# rgbwa_controller.net
KiCad netlist of a schematic drawn in EAGLE
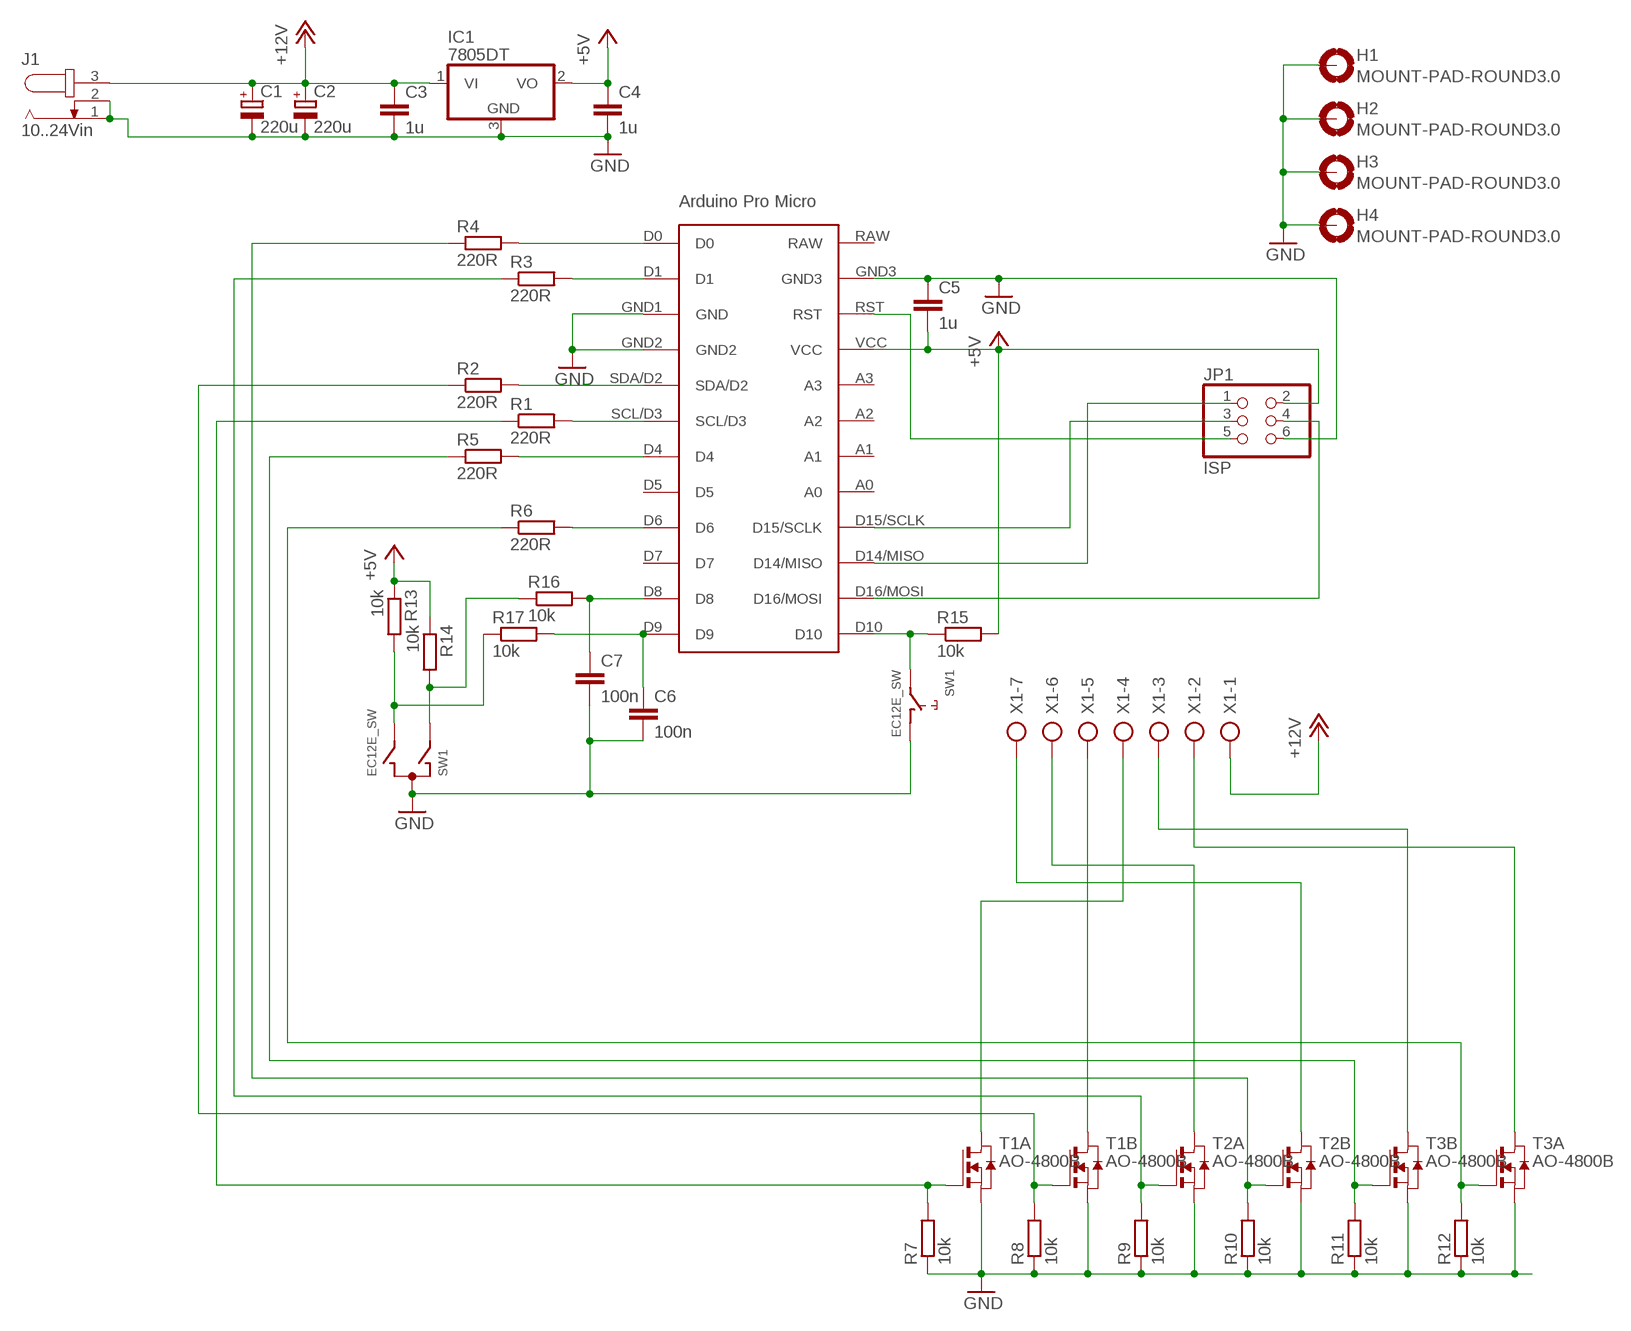
[diagram p0: schematic, sheet 1]

(export (version "E")
  (design (tool "Eeschema 10.0.6"))
  (components
    (comp (ref "C1")
      (value "220u")
      (footprint "eagle-import:150CLZ-1010")
      (libsource (lib "eagle-import") (part "CPOL-EU150CLZ-1010"))
    )
    (comp (ref "C2")
      (value "220u")
      (footprint "eagle-import:150CLZ-1010")
      (libsource (lib "eagle-import") (part "CPOL-EU150CLZ-1010"))
    )
    (comp (ref "C3")
      (value "1u")
      (footprint "eagle-import:C1206")
      (libsource (lib "eagle-import") (part "C-EUC1206"))
    )
    (comp (ref "C4")
      (value "1u")
      (footprint "eagle-import:C1206")
      (libsource (lib "eagle-import") (part "C-EUC1206"))
    )
    (comp (ref "C5")
      (value "1u")
      (footprint "eagle-import:C1206")
      (libsource (lib "eagle-import") (part "C-EUC1206"))
    )
    (comp (ref "C6")
      (value "100n")
      (footprint "eagle-import:C0805")
      (libsource (lib "eagle-import") (part "C-EUC0805"))
    )
    (comp (ref "C7")
      (value "100n")
      (footprint "eagle-import:C0805")
      (libsource (lib "eagle-import") (part "C-EUC0805"))
    )
    (comp (ref "H1")
      (value "MOUNT-PAD-ROUND3.0")
      (footprint "eagle-import:3,0-PAD")
      (libsource (lib "eagle-import") (part "MOUNT-PAD-ROUND3.0"))
    )
    (comp (ref "H2")
      (value "MOUNT-PAD-ROUND3.0")
      (footprint "eagle-import:3,0-PAD")
      (libsource (lib "eagle-import") (part "MOUNT-PAD-ROUND3.0"))
    )
    (comp (ref "H3")
      (value "MOUNT-PAD-ROUND3.0")
      (footprint "eagle-import:3,0-PAD")
      (libsource (lib "eagle-import") (part "MOUNT-PAD-ROUND3.0"))
    )
    (comp (ref "H4")
      (value "MOUNT-PAD-ROUND3.0")
      (footprint "eagle-import:3,0-PAD")
      (libsource (lib "eagle-import") (part "MOUNT-PAD-ROUND3.0"))
    )
    (comp (ref "IC1")
      (value "7805DT")
      (footprint "eagle-import:TO252")
      (libsource (lib "eagle-import") (part "78DT05"))
    )
    (comp (ref "J1")
      (value "10..24Vin")
      (footprint "eagle-import:SPC4078")
      (libsource (lib "eagle-import") (part "JACK-PLUG1"))
    )
    (comp (ref "JP1")
      (value "ISP")
      (footprint "eagle-import:2X03")
      (libsource (lib "eagle-import") (part "PINHD-2X3"))
    )
    (comp (ref "R1")
      (value "220R")
      (footprint "eagle-import:M0805")
      (libsource (lib "eagle-import") (part "R-EU_M0805"))
    )
    (comp (ref "R2")
      (value "220R")
      (footprint "eagle-import:M0805")
      (libsource (lib "eagle-import") (part "R-EU_M0805"))
    )
    (comp (ref "R3")
      (value "220R")
      (footprint "eagle-import:M0805")
      (libsource (lib "eagle-import") (part "R-EU_M0805"))
    )
    (comp (ref "R4")
      (value "220R")
      (footprint "eagle-import:M0805")
      (libsource (lib "eagle-import") (part "R-EU_M0805"))
    )
    (comp (ref "R5")
      (value "220R")
      (footprint "eagle-import:M0805")
      (libsource (lib "eagle-import") (part "R-EU_M0805"))
    )
    (comp (ref "R6")
      (value "220R")
      (footprint "eagle-import:M0805")
      (libsource (lib "eagle-import") (part "R-EU_M0805"))
    )
    (comp (ref "R7")
      (value "10k")
      (footprint "eagle-import:M0805")
      (libsource (lib "eagle-import") (part "R-EU_M0805"))
    )
    (comp (ref "R8")
      (value "10k")
      (footprint "eagle-import:M0805")
      (libsource (lib "eagle-import") (part "R-EU_M0805"))
    )
    (comp (ref "R9")
      (value "10k")
      (footprint "eagle-import:M0805")
      (libsource (lib "eagle-import") (part "R-EU_M0805"))
    )
    (comp (ref "R10")
      (value "10k")
      (footprint "eagle-import:M0805")
      (libsource (lib "eagle-import") (part "R-EU_M0805"))
    )
    (comp (ref "R11")
      (value "10k")
      (footprint "eagle-import:M0805")
      (libsource (lib "eagle-import") (part "R-EU_M0805"))
    )
    (comp (ref "R12")
      (value "10k")
      (footprint "eagle-import:M0805")
      (libsource (lib "eagle-import") (part "R-EU_M0805"))
    )
    (comp (ref "R13")
      (value "10k")
      (footprint "eagle-import:M0805")
      (libsource (lib "eagle-import") (part "R-EU_M0805"))
    )
    (comp (ref "R14")
      (value "10k")
      (footprint "eagle-import:M0805")
      (libsource (lib "eagle-import") (part "R-EU_M0805"))
    )
    (comp (ref "R15")
      (value "10k")
      (footprint "eagle-import:M0805")
      (libsource (lib "eagle-import") (part "R-EU_M0805"))
    )
    (comp (ref "R16")
      (value "10k")
      (footprint "eagle-import:M0805")
      (libsource (lib "eagle-import") (part "R-EU_M0805"))
    )
    (comp (ref "R17")
      (value "10k")
      (footprint "eagle-import:M0805")
      (libsource (lib "eagle-import") (part "R-EU_M0805"))
    )
    (comp (ref "SW1")
      (value "EC12E_SW")
      (footprint "eagle-import:ALPS_EC12E_SW")
      (fields (field (name "MPN") "EC12E2424407"))
      (libsource (lib "eagle-import") (part "EC12E_SW"))
    )
    (comp (ref "T1")
      (value "AO-4800B")
      (footprint "eagle-import:SM8")
      (libsource (lib "eagle-import") (part "NMOS2SM8"))
    )
    (comp (ref "T2")
      (value "AO-4800B")
      (footprint "eagle-import:SM8")
      (libsource (lib "eagle-import") (part "NMOS2SM8"))
    )
    (comp (ref "T3")
      (value "AO-4800B")
      (footprint "eagle-import:SM8")
      (libsource (lib "eagle-import") (part "NMOS2SM8"))
    )
    (comp (ref "U$1")
      (value "PROMICRO")
      (footprint "eagle-import:PROMICRO")
      (libsource (lib "eagle-import") (part "PROMICRO"))
    )
    (comp (ref "X1")
      (value "AK300/7")
      (footprint "eagle-import:AK300_7")
      (libsource (lib "eagle-import") (part "AK300/7"))
    )
  )
  (nets
    (net (code "1") (name "+5V") (class "Default")
      (node (ref "C4") (pin "1") (pinfunction "1_1") (pintype "passive"))
      (node (ref "C5") (pin "2") (pinfunction "2_2") (pintype "passive"))
      (node (ref "IC1") (pin "2") (pinfunction "VO_2") (pintype "passive"))
      (node (ref "JP1") (pin "2") (pinfunction "2_2") (pintype "passive"))
      (node (ref "R13") (pin "1") (pinfunction "1_1") (pintype "passive"))
      (node (ref "R14") (pin "1") (pinfunction "1_1") (pintype "passive"))
      (node (ref "R15") (pin "2") (pinfunction "2_2") (pintype "passive"))
      (node (ref "U$1") (pin "VCC") (pinfunction "VCC_VCC") (pintype "bidirectional"))
    )
    (net (code "2") (name "+12V") (class "Default")
      (node (ref "C1") (pin "+") (pinfunction "+_+") (pintype "passive"))
      (node (ref "C2") (pin "+") (pinfunction "+_+") (pintype "passive"))
      (node (ref "C3") (pin "1") (pinfunction "1_1") (pintype "passive"))
      (node (ref "IC1") (pin "1") (pinfunction "VI_1") (pintype "input"))
      (node (ref "J1") (pin "3") (pinfunction "3_3") (pintype "passive"))
      (node (ref "X1") (pin "1") (pinfunction "KL_1") (pintype "passive"))
    )
    (net (code "3") (name "GND") (class "Default")
      (node (ref "C1") (pin "-") (pinfunction "-_-") (pintype "passive"))
      (node (ref "C2") (pin "-") (pinfunction "-_-") (pintype "passive"))
      (node (ref "C3") (pin "2") (pinfunction "2_2") (pintype "passive"))
      (node (ref "C4") (pin "2") (pinfunction "2_2") (pintype "passive"))
      (node (ref "C5") (pin "1") (pinfunction "1_1") (pintype "passive"))
      (node (ref "C6") (pin "2") (pinfunction "2_2") (pintype "passive"))
      (node (ref "C7") (pin "2") (pinfunction "2_2") (pintype "passive"))
      (node (ref "H1") (pin "B3,0") (pinfunction "MOUNT_B3,0") (pintype "passive"))
      (node (ref "H2") (pin "B3,0") (pinfunction "MOUNT_B3,0") (pintype "passive"))
      (node (ref "H3") (pin "B3,0") (pinfunction "MOUNT_B3,0") (pintype "passive"))
      (node (ref "H4") (pin "B3,0") (pinfunction "MOUNT_B3,0") (pintype "passive"))
      (node (ref "IC1") (pin "3") (pinfunction "GND_3") (pintype "passive"))
      (node (ref "J1") (pin "1") (pinfunction "1_1") (pintype "passive"))
      (node (ref "J1") (pin "2") (pinfunction "2_2") (pintype "passive"))
      (node (ref "JP1") (pin "6") (pinfunction "6_6") (pintype "passive"))
      (node (ref "R10") (pin "1") (pinfunction "1_1") (pintype "passive"))
      (node (ref "R11") (pin "1") (pinfunction "1_1") (pintype "passive"))
      (node (ref "R12") (pin "1") (pinfunction "1_1") (pintype "passive"))
      (node (ref "R7") (pin "1") (pinfunction "1_1") (pintype "passive"))
      (node (ref "R8") (pin "1") (pinfunction "1_1") (pintype "passive"))
      (node (ref "R9") (pin "1") (pinfunction "1_1") (pintype "passive"))
      (node (ref "SW1") (pin "C") (pinfunction "C_C") (pintype "passive"))
      (node (ref "SW1") (pin "D") (pinfunction "1_D") (pintype "passive"))
      (node (ref "T1") (pin "1") (pinfunction "S_1") (pintype "passive"))
      (node (ref "T1") (pin "3") (pinfunction "S_3") (pintype "passive"))
      (node (ref "T2") (pin "1") (pinfunction "S_1") (pintype "passive"))
      (node (ref "T2") (pin "3") (pinfunction "S_3") (pintype "passive"))
      (node (ref "T3") (pin "1") (pinfunction "S_1") (pintype "passive"))
      (node (ref "T3") (pin "3") (pinfunction "S_3") (pintype "passive"))
      (node (ref "U$1") (pin "GND1") (pinfunction "GND_GND1") (pintype "bidirectional"))
      (node (ref "U$1") (pin "GND2") (pinfunction "GND2_GND2") (pintype "bidirectional"))
      (node (ref "U$1") (pin "GND3") (pinfunction "GND3_GND3") (pintype "bidirectional"))
    )
    (net (code "4") (name "Net-(C6-Pad1)") (class "Default")
      (node (ref "C6") (pin "1") (pinfunction "1_1") (pintype "passive"))
      (node (ref "R17") (pin "2") (pinfunction "2_2") (pintype "passive"))
      (node (ref "U$1") (pin "D9") (pinfunction "D9_D9") (pintype "bidirectional"))
    )
    (net (code "5") (name "Net-(C7-Pad1)") (class "Default")
      (node (ref "C7") (pin "1") (pinfunction "1_1") (pintype "passive"))
      (node (ref "R16") (pin "2") (pinfunction "2_2") (pintype "passive"))
      (node (ref "U$1") (pin "D8") (pinfunction "D8_D8") (pintype "bidirectional"))
    )
    (net (code "6") (name "Net-(JP1-Pad1)") (class "Default")
      (node (ref "JP1") (pin "1") (pinfunction "1_1") (pintype "passive"))
      (node (ref "U$1") (pin "D14/MISO") (pinfunction "D14/MISO_D14/MISO") (pintype "bidirectional"))
    )
    (net (code "7") (name "Net-(JP1-Pad3)") (class "Default")
      (node (ref "JP1") (pin "3") (pinfunction "3_3") (pintype "passive"))
      (node (ref "U$1") (pin "D15/SCLK") (pinfunction "D15/SCLK_D15/SCLK") (pintype "bidirectional"))
    )
    (net (code "8") (name "Net-(JP1-Pad4)") (class "Default")
      (node (ref "JP1") (pin "4") (pinfunction "4_4") (pintype "passive"))
      (node (ref "U$1") (pin "D16/MOSI") (pinfunction "D16/MOSI_D16/MOSI") (pintype "bidirectional"))
    )
    (net (code "9") (name "Net-(JP1-Pad5)") (class "Default")
      (node (ref "JP1") (pin "5") (pinfunction "5_5") (pintype "passive"))
      (node (ref "U$1") (pin "RST") (pinfunction "RST_RST") (pintype "bidirectional"))
    )
    (net (code "10") (name "Net-(R1-Pad2)") (class "Default")
      (node (ref "R1") (pin "2") (pinfunction "2_2") (pintype "passive"))
      (node (ref "U$1") (pin "SCL/D3") (pinfunction "SCL/D3_SCL/D3") (pintype "bidirectional"))
    )
    (net (code "11") (name "Net-(R2-Pad2)") (class "Default")
      (node (ref "R2") (pin "2") (pinfunction "2_2") (pintype "passive"))
      (node (ref "U$1") (pin "SDA/D2") (pinfunction "SDA/D2_SDA/D2") (pintype "bidirectional"))
    )
    (net (code "12") (name "Net-(R3-Pad2)") (class "Default")
      (node (ref "R3") (pin "2") (pinfunction "2_2") (pintype "passive"))
      (node (ref "U$1") (pin "D1") (pinfunction "D1_D1") (pintype "bidirectional"))
    )
    (net (code "13") (name "Net-(R4-Pad2)") (class "Default")
      (node (ref "R4") (pin "2") (pinfunction "2_2") (pintype "passive"))
      (node (ref "U$1") (pin "D0") (pinfunction "D0_D0") (pintype "bidirectional"))
    )
    (net (code "14") (name "Net-(R5-Pad2)") (class "Default")
      (node (ref "R5") (pin "2") (pinfunction "2_2") (pintype "passive"))
      (node (ref "U$1") (pin "D4") (pinfunction "D4_D4") (pintype "bidirectional"))
    )
    (net (code "15") (name "Net-(R6-Pad2)") (class "Default")
      (node (ref "R6") (pin "2") (pinfunction "2_2") (pintype "passive"))
      (node (ref "U$1") (pin "D6") (pinfunction "D6_D6") (pintype "bidirectional"))
    )
    (net (code "16") (name "Net-(R13-Pad2)") (class "Default")
      (node (ref "R13") (pin "2") (pinfunction "2_2") (pintype "passive"))
      (node (ref "R17") (pin "1") (pinfunction "1_1") (pintype "passive"))
      (node (ref "SW1") (pin "B") (pinfunction "B_B") (pintype "passive"))
    )
    (net (code "17") (name "Net-(R14-Pad2)") (class "Default")
      (node (ref "R14") (pin "2") (pinfunction "2_2") (pintype "passive"))
      (node (ref "R16") (pin "1") (pinfunction "1_1") (pintype "passive"))
      (node (ref "SW1") (pin "A") (pinfunction "A_A") (pintype "passive"))
    )
    (net (code "18") (name "Net-(SW1B-2)") (class "Default")
      (node (ref "R15") (pin "1") (pinfunction "1_1") (pintype "passive"))
      (node (ref "SW1") (pin "E") (pinfunction "2_E") (pintype "passive"))
      (node (ref "U$1") (pin "D10") (pinfunction "D10_D10") (pintype "bidirectional"))
    )
    (net (code "19") (name "Net-(T1A-G)") (class "Default")
      (node (ref "R1") (pin "1") (pinfunction "1_1") (pintype "passive"))
      (node (ref "R7") (pin "2") (pinfunction "2_2") (pintype "passive"))
      (node (ref "T1") (pin "2") (pinfunction "G_2") (pintype "passive"))
    )
    (net (code "20") (name "Net-(T1B-G)") (class "Default")
      (node (ref "R2") (pin "1") (pinfunction "1_1") (pintype "passive"))
      (node (ref "R8") (pin "2") (pinfunction "2_2") (pintype "passive"))
      (node (ref "T1") (pin "4") (pinfunction "G_4") (pintype "passive"))
    )
    (net (code "21") (name "Net-(T2A-G)") (class "Default")
      (node (ref "R3") (pin "1") (pinfunction "1_1") (pintype "passive"))
      (node (ref "R9") (pin "2") (pinfunction "2_2") (pintype "passive"))
      (node (ref "T2") (pin "2") (pinfunction "G_2") (pintype "passive"))
    )
    (net (code "22") (name "Net-(T2B-G)") (class "Default")
      (node (ref "R10") (pin "2") (pinfunction "2_2") (pintype "passive"))
      (node (ref "R4") (pin "1") (pinfunction "1_1") (pintype "passive"))
      (node (ref "T2") (pin "4") (pinfunction "G_4") (pintype "passive"))
    )
    (net (code "23") (name "Net-(T3A-G)") (class "Default")
      (node (ref "R12") (pin "2") (pinfunction "2_2") (pintype "passive"))
      (node (ref "R6") (pin "1") (pinfunction "1_1") (pintype "passive"))
      (node (ref "T3") (pin "2") (pinfunction "G_2") (pintype "passive"))
    )
    (net (code "24") (name "Net-(T3B-G)") (class "Default")
      (node (ref "R11") (pin "2") (pinfunction "2_2") (pintype "passive"))
      (node (ref "R5") (pin "1") (pinfunction "1_1") (pintype "passive"))
      (node (ref "T3") (pin "4") (pinfunction "G_4") (pintype "passive"))
    )
    (net (code "25") (name "Net-(X1B-KL)") (class "Default")
      (node (ref "T3") (pin "7") (pinfunction "D_7") (pintype "passive"))
      (node (ref "T3") (pin "8") (pinfunction "D_8") (pintype "passive"))
      (node (ref "X1") (pin "2") (pinfunction "KL_2") (pintype "passive"))
    )
    (net (code "26") (name "Net-(X1C-KL)") (class "Default")
      (node (ref "T3") (pin "5") (pinfunction "D_5") (pintype "passive"))
      (node (ref "T3") (pin "6") (pinfunction "D_6") (pintype "passive"))
      (node (ref "X1") (pin "3") (pinfunction "KL_3") (pintype "passive"))
    )
    (net (code "27") (name "Net-(X1D-KL)") (class "Default")
      (node (ref "T1") (pin "7") (pinfunction "D_7") (pintype "passive"))
      (node (ref "T1") (pin "8") (pinfunction "D_8") (pintype "passive"))
      (node (ref "X1") (pin "4") (pinfunction "KL_4") (pintype "passive"))
    )
    (net (code "28") (name "Net-(X1E-KL)") (class "Default")
      (node (ref "T1") (pin "5") (pinfunction "D_5") (pintype "passive"))
      (node (ref "T1") (pin "6") (pinfunction "D_6") (pintype "passive"))
      (node (ref "X1") (pin "5") (pinfunction "KL_5") (pintype "passive"))
    )
    (net (code "29") (name "Net-(X1F-KL)") (class "Default")
      (node (ref "T2") (pin "7") (pinfunction "D_7") (pintype "passive"))
      (node (ref "T2") (pin "8") (pinfunction "D_8") (pintype "passive"))
      (node (ref "X1") (pin "6") (pinfunction "KL_6") (pintype "passive"))
    )
    (net (code "30") (name "Net-(X1G-KL)") (class "Default")
      (node (ref "T2") (pin "5") (pinfunction "D_5") (pintype "passive"))
      (node (ref "T2") (pin "6") (pinfunction "D_6") (pintype "passive"))
      (node (ref "X1") (pin "7") (pinfunction "KL_7") (pintype "passive"))
    )
    (net (code "31") (name "unconnected-(U$1-PadA0)") (class "Default")
      (node (ref "U$1") (pin "A0") (pinfunction "A0_A0") (pintype "bidirectional"))
    )
    (net (code "32") (name "unconnected-(U$1-PadA1)") (class "Default")
      (node (ref "U$1") (pin "A1") (pinfunction "A1_A1") (pintype "bidirectional"))
    )
    (net (code "33") (name "unconnected-(U$1-PadA2)") (class "Default")
      (node (ref "U$1") (pin "A2") (pinfunction "A2_A2") (pintype "bidirectional"))
    )
    (net (code "34") (name "unconnected-(U$1-PadA3)") (class "Default")
      (node (ref "U$1") (pin "A3") (pinfunction "A3_A3") (pintype "bidirectional"))
    )
    (net (code "35") (name "unconnected-(U$1-PadD5)") (class "Default")
      (node (ref "U$1") (pin "D5") (pinfunction "D5_D5") (pintype "bidirectional"))
    )
    (net (code "36") (name "unconnected-(U$1-PadD7)") (class "Default")
      (node (ref "U$1") (pin "D7") (pinfunction "D7_D7") (pintype "bidirectional"))
    )
    (net (code "37") (name "unconnected-(U$1-PadRAW)") (class "Default")
      (node (ref "U$1") (pin "RAW") (pinfunction "RAW_RAW") (pintype "bidirectional"))
    )
  )
)
